# Source.net
KiCad netlist of a schematic drawn in Altium Designer
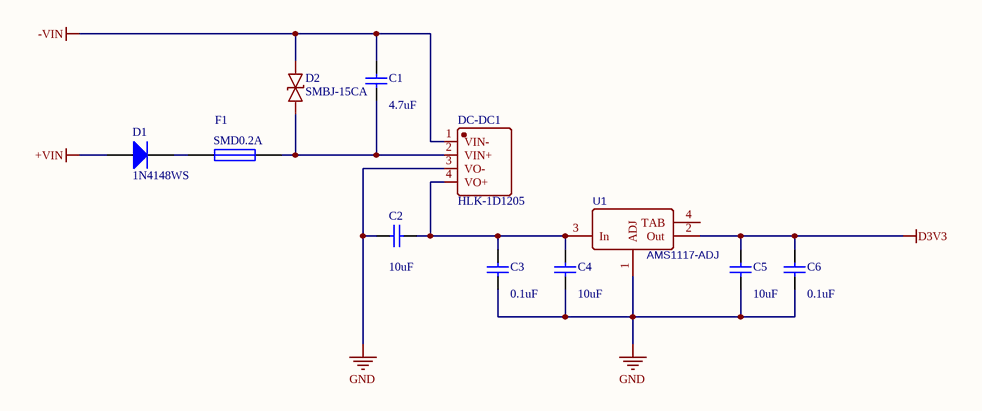
[diagram p0: Source.SchDoc]

(export (version "E")
  (design (tool "Eeschema 10.0.6"))
  (components
    (comp (ref "C1")
      (value "4.7uF")
      (footprint "C1206")
      (description "Capacitor (Semiconductor SIM Model)")
      (fields (field (name "PUBLISHER") "Altium Limited"))
      (libsource (lib "Miscellaneous Devices") (part "Cap Semi"))
    )
    (comp (ref "C2")
      (value "10uF")
      (footprint "C1206")
      (description "Capacitor (Semiconductor SIM Model)")
      (fields (field (name "PUBLISHER") "Altium Limited"))
      (libsource (lib "Miscellaneous Devices") (part "Cap Semi"))
    )
    (comp (ref "C3")
      (value "0.1uF")
      (footprint "C1206")
      (description "Capacitor (Semiconductor SIM Model)")
      (fields (field (name "PUBLISHER") "Altium Limited"))
      (libsource (lib "Miscellaneous Devices") (part "Cap Semi"))
    )
    (comp (ref "C4")
      (value "10uF")
      (footprint "C1206")
      (description "Capacitor (Semiconductor SIM Model)")
      (fields (field (name "PUBLISHER") "Altium Limited"))
      (libsource (lib "Miscellaneous Devices") (part "Cap Semi"))
    )
    (comp (ref "C5")
      (value "10uF")
      (footprint "C1206")
      (description "Capacitor (Semiconductor SIM Model)")
      (fields (field (name "PUBLISHER") "Altium Limited"))
      (libsource (lib "Miscellaneous Devices") (part "Cap Semi"))
    )
    (comp (ref "C6")
      (value "0.1uF")
      (footprint "C1206")
      (description "Capacitor (Semiconductor SIM Model)")
      (fields (field (name "PUBLISHER") "Altium Limited"))
      (libsource (lib "Miscellaneous Devices") (part "Cap Semi"))
    )
    (comp (ref "D1")
      (value "1N4148WS")
      (footprint "SOD-323")
      (description "二极管")
      (libsource (lib "02-Miscellaneous_Devices_ZSF_Library") (part "1N4148WS_SOD-323"))
    )
    (comp (ref "D2")
      (value "SMBJ-15CA")
      (footprint "SMB_L4.6-W3.6-LS5.3-BI")
      (libsource (lib "NBIoT") (part "SMBJ-XXCA"))
    )
    (comp (ref "DC-DC1")
      (value "HLK-1D1205")
      (footprint "PWRM-TH_HLK-1DXXXX")
      (libsource (lib "NBIoT") (part "HLK-1D12XX"))
    )
    (comp (ref "SMD0.2A")
      (value "F1")
      (footprint "C1206")
      (description "Fuse")
      (fields (field (name "PUBLISHER") "Altium Limited"))
      (libsource (lib "Miscellaneous Devices") (part "Fuse 1"))
    )
    (comp (ref "U1")
      (value "AMS1117-ADJ")
      (footprint "SOT-223_L6.7-W3.5-P2.30-BR")
      (fields (field (name "BOM_SUPPLIER PART") "C6188") (field (name "CONTRIBUTOR") "GerryChen"))
      (libsource (lib "NBIoT") (part "AMS1117-ADJ"))
    )
  )
  (nets
    (net (code "1") (name "+VIN") (class "Default")
      (node (ref "D1") (pin "1") (pinfunction "A_1") (pintype "passive"))
    )
    (net (code "2") (name "-VIN") (class "Default")
      (node (ref "C1") (pin "2") (pinfunction "2_2") (pintype "passive"))
      (node (ref "D2") (pin "2") (pinfunction "2_2") (pintype "passive"))
      (node (ref "DC-DC1") (pin "1") (pinfunction "VIN-_1") (pintype "passive"))
    )
    (net (code "3") (name "D3V3") (class "Default")
      (node (ref "C5") (pin "2") (pinfunction "2_2") (pintype "passive"))
      (node (ref "C6") (pin "2") (pinfunction "2_2") (pintype "passive"))
      (node (ref "U1") (pin "2") (pinfunction "Out_2") (pintype "passive"))
    )
    (net (code "4") (name "GND") (class "Default")
      (node (ref "C2") (pin "1") (pinfunction "1_1") (pintype "passive"))
      (node (ref "C3") (pin "2") (pinfunction "2_2") (pintype "passive"))
      (node (ref "C4") (pin "1") (pinfunction "1_1") (pintype "passive"))
      (node (ref "C5") (pin "1") (pinfunction "1_1") (pintype "passive"))
      (node (ref "C6") (pin "1") (pinfunction "1_1") (pintype "passive"))
      (node (ref "DC-DC1") (pin "3") (pinfunction "VO-_3") (pintype "passive"))
      (node (ref "U1") (pin "1") (pinfunction "ADJ_1") (pintype "passive"))
    )
    (net (code "5") (name "Net-(D1-K)") (class "Default")
      (node (ref "D1") (pin "2") (pinfunction "K_2") (pintype "passive"))
      (node (ref "SMD0.2A") (pin "1") (pinfunction "1_1") (pintype "passive"))
    )
    (net (code "6") (name "Net-(DC-DC1-VIN+)") (class "Default")
      (node (ref "C1") (pin "1") (pinfunction "1_1") (pintype "passive"))
      (node (ref "D2") (pin "1") (pinfunction "1_1") (pintype "passive"))
      (node (ref "DC-DC1") (pin "2") (pinfunction "VIN+_2") (pintype "passive"))
      (node (ref "SMD0.2A") (pin "2") (pinfunction "2_2") (pintype "passive"))
    )
    (net (code "7") (name "Net-(DC-DC1-VO+)") (class "Default")
      (node (ref "C2") (pin "2") (pinfunction "2_2") (pintype "passive"))
      (node (ref "C3") (pin "1") (pinfunction "1_1") (pintype "passive"))
      (node (ref "C4") (pin "2") (pinfunction "2_2") (pintype "passive"))
      (node (ref "DC-DC1") (pin "4") (pinfunction "VO+_4") (pintype "passive"))
      (node (ref "U1") (pin "3") (pinfunction "In_3") (pintype "passive"))
    )
    (net (code "8") (name "unconnected-(U1-TAB-Pad4)") (class "Default")
      (node (ref "U1") (pin "4") (pinfunction "TAB_4") (pintype "passive"))
    )
  )
)
